# foe-scale2.net
KiCad netlist of a schematic drawn in EAGLE
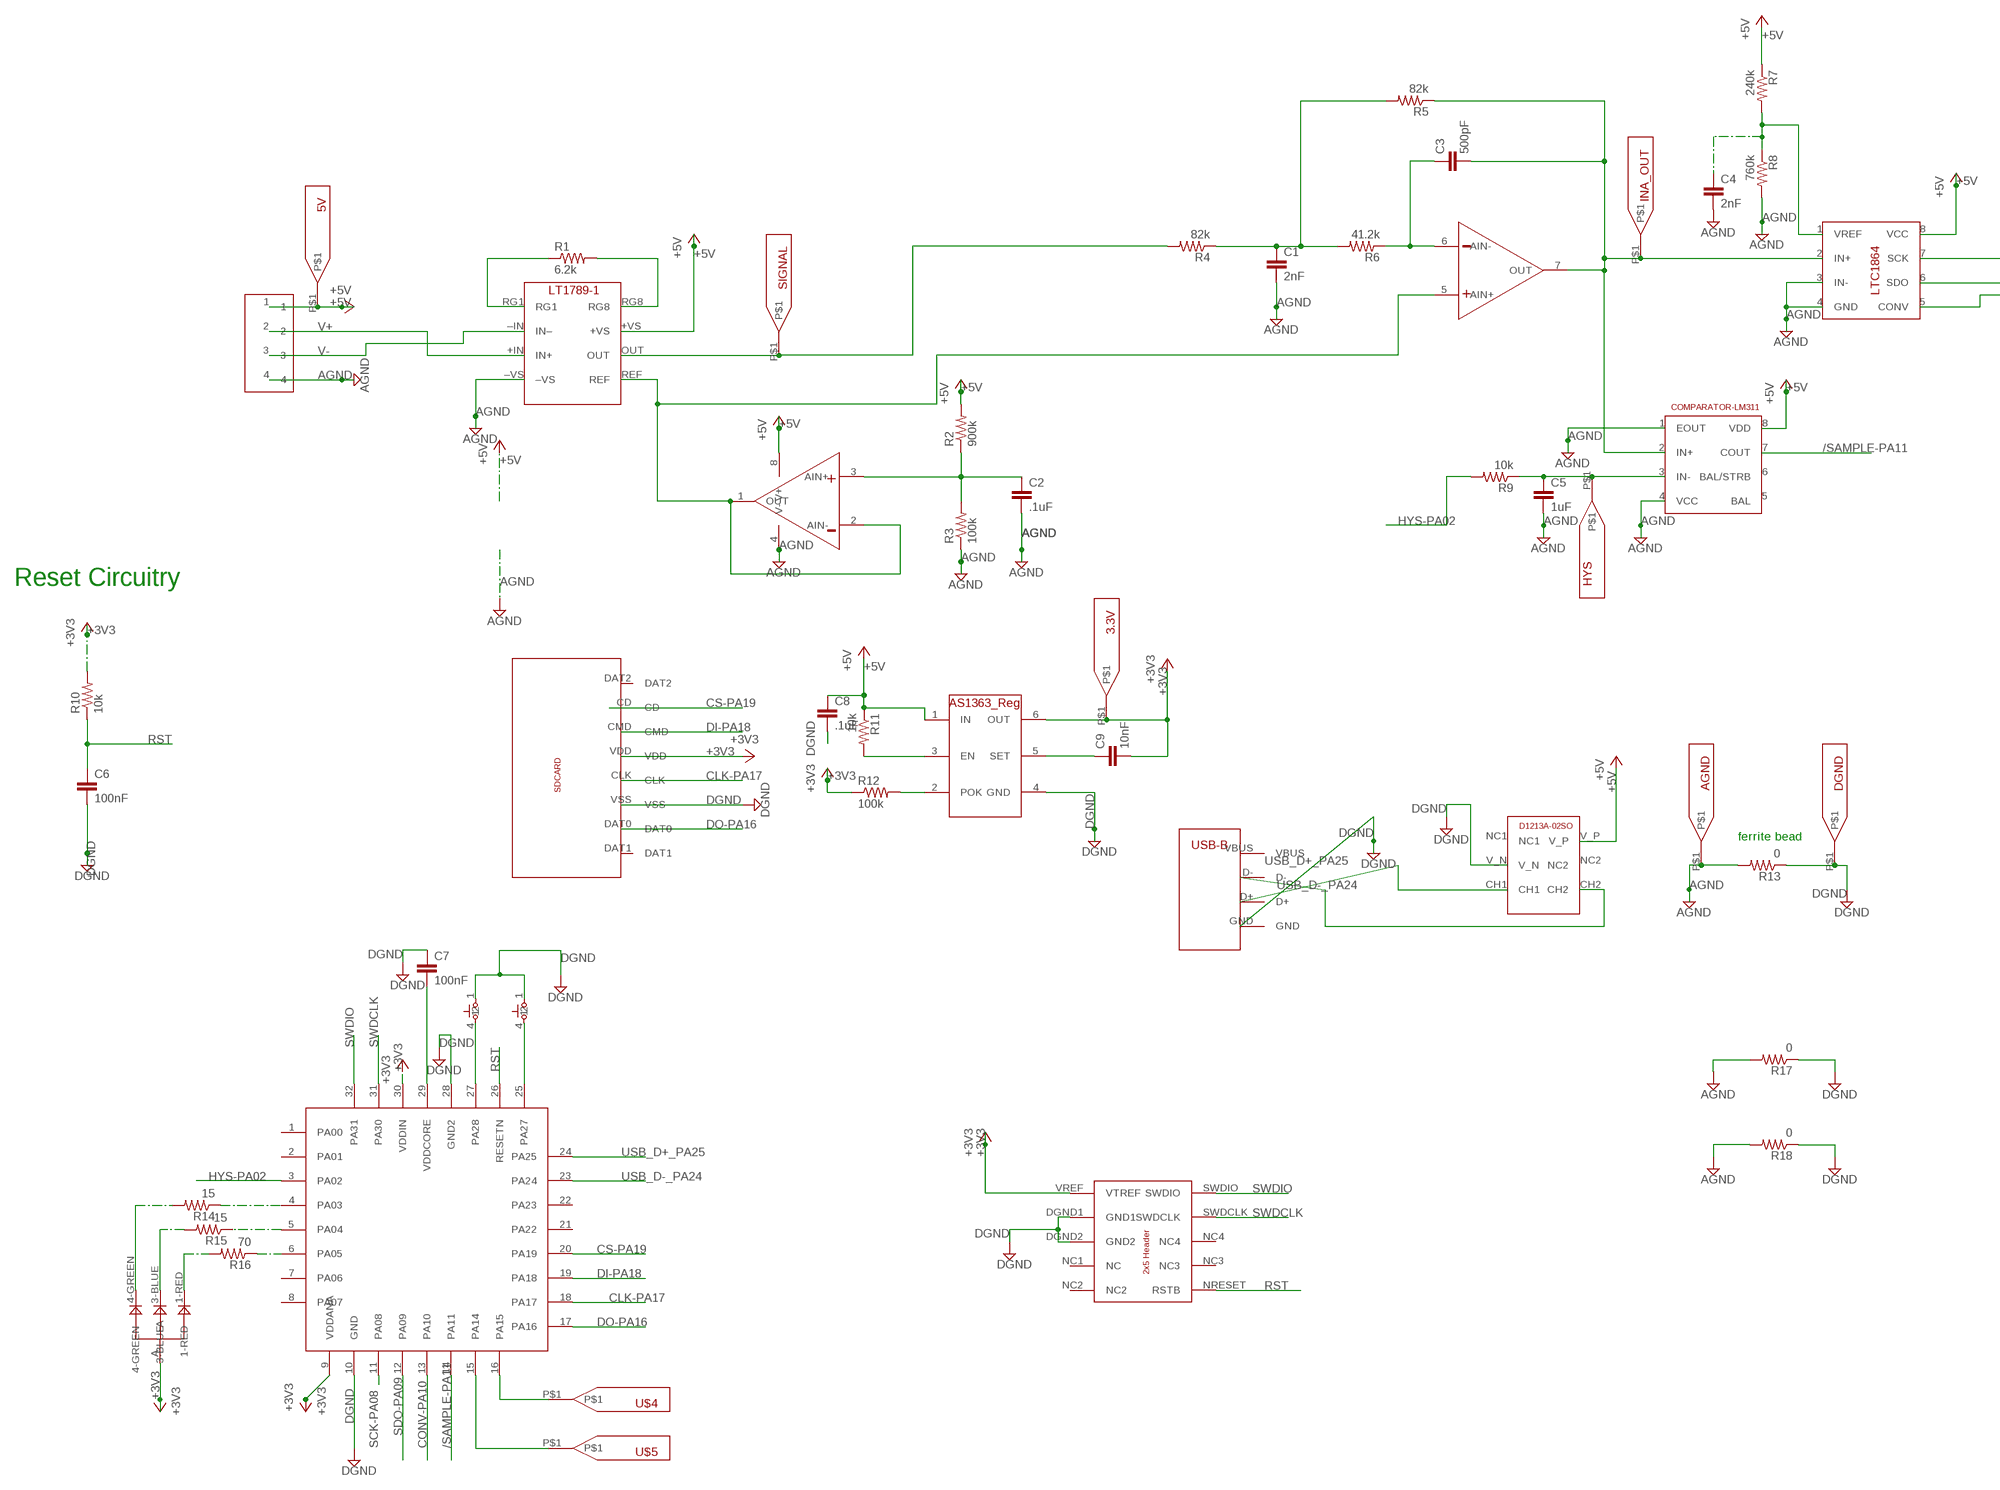
[diagram p0: schematic, sheet 1, part 1 of 2]
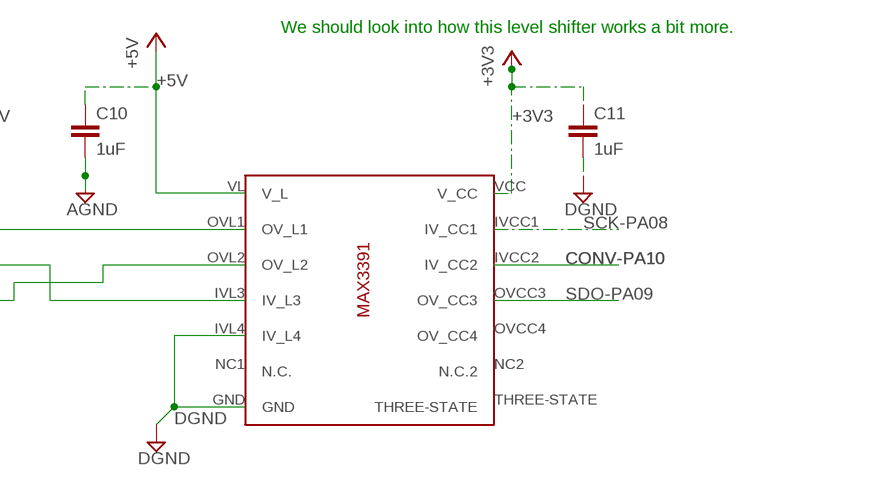
[diagram p1: schematic, sheet 1, part 2 of 2]

(export (version "E")
  (design (tool "Eeschema 10.0.6"))
  (components
    (comp (ref "3.3V")
      (value "TEST_POINT")
      (footprint "eagle-import:TEST_POINT")
      (libsource (lib "eagle-import") (part "TEST_POINT"))
    )
    (comp (ref "5V")
      (value "TEST_POINT")
      (footprint "eagle-import:TEST_POINT")
      (libsource (lib "eagle-import") (part "TEST_POINT"))
    )
    (comp (ref "AGND")
      (value "TEST_POINT")
      (footprint "eagle-import:TEST_POINT")
      (libsource (lib "eagle-import") (part "TEST_POINT"))
    )
    (comp (ref "AS1363")
      (value "3.3V_AS1363")
      (footprint "eagle-import:SOT23-6")
      (libsource (lib "eagle-import") (part "3.3V_AS1363"))
    )
    (comp (ref "C1")
      (value "2nF")
      (footprint "eagle-import:C0805K")
      (libsource (lib "eagle-import") (part "C-EUC0805K"))
    )
    (comp (ref "C2")
      (value ".1uF")
      (footprint "eagle-import:C0805K")
      (libsource (lib "eagle-import") (part "C-EUC0805K"))
    )
    (comp (ref "C3")
      (value "500pF")
      (footprint "eagle-import:C0805K")
      (libsource (lib "eagle-import") (part "C-EUC0805K"))
    )
    (comp (ref "C4")
      (value "2nF")
      (footprint "eagle-import:C0805K")
      (libsource (lib "eagle-import") (part "C-EUC0805K"))
    )
    (comp (ref "C5")
      (value "1uF")
      (footprint "eagle-import:C0805K")
      (libsource (lib "eagle-import") (part "C-EUC0805K"))
    )
    (comp (ref "C6")
      (value "100nF")
      (footprint "eagle-import:C0805K")
      (libsource (lib "eagle-import") (part "C-EUC0805K"))
    )
    (comp (ref "C7")
      (value "100nF")
      (footprint "eagle-import:C0805K")
      (libsource (lib "eagle-import") (part "C-EUC0805K"))
    )
    (comp (ref "C8")
      (value ".1uF")
      (footprint "eagle-import:C0805K")
      (libsource (lib "eagle-import") (part "C-EUC0805K"))
    )
    (comp (ref "C9")
      (value "10nF")
      (footprint "eagle-import:C0805K")
      (libsource (lib "eagle-import") (part "C-EUC0805K"))
    )
    (comp (ref "C10")
      (value "1uF")
      (footprint "eagle-import:C0805K")
      (libsource (lib "eagle-import") (part "C-EUC0805K"))
    )
    (comp (ref "C11")
      (value "1uF")
      (footprint "eagle-import:C0805K")
      (libsource (lib "eagle-import") (part "C-EUC0805K"))
    )
    (comp (ref "D1")
      (value "D1213A-DIODE-ARRAY")
      (footprint "eagle-import:SOT26-DIODE-ARRAY")
      (libsource (lib "eagle-import") (part "D1213A-DIODE-ARRAY"))
    )
    (comp (ref "DBG1")
      (value "DEBUGHEAD")
      (footprint "eagle-import:DEBUGHEAD")
      (libsource (lib "eagle-import") (part "DEBUGHEAD"))
    )
    (comp (ref "DGND")
      (value "TEST_POINT")
      (footprint "eagle-import:TEST_POINT")
      (libsource (lib "eagle-import") (part "TEST_POINT"))
    )
    (comp (ref "HYS")
      (value "TEST_POINT")
      (footprint "eagle-import:TEST_POINT")
      (libsource (lib "eagle-import") (part "TEST_POINT"))
    )
    (comp (ref "INA_OUT")
      (value "TEST_POINT")
      (footprint "eagle-import:TEST_POINT")
      (libsource (lib "eagle-import") (part "TEST_POINT"))
    )
    (comp (ref "R1")
      (value "6.2k")
      (footprint "eagle-import:R0805")
      (libsource (lib "eagle-import") (part "R-US_R0805"))
    )
    (comp (ref "R2")
      (value "900k")
      (footprint "eagle-import:R0805")
      (libsource (lib "eagle-import") (part "R-US_R0805"))
    )
    (comp (ref "R3")
      (value "100k")
      (footprint "eagle-import:R0805")
      (libsource (lib "eagle-import") (part "R-US_R0805"))
    )
    (comp (ref "R4")
      (value "82k")
      (footprint "eagle-import:R0805")
      (libsource (lib "eagle-import") (part "R-US_R0805"))
    )
    (comp (ref "R5")
      (value "82k")
      (footprint "eagle-import:R0805")
      (libsource (lib "eagle-import") (part "R-US_R0805"))
    )
    (comp (ref "R6")
      (value "41.2k")
      (footprint "eagle-import:R0805")
      (libsource (lib "eagle-import") (part "R-US_R0805"))
    )
    (comp (ref "R7")
      (value "240k")
      (footprint "eagle-import:R0805")
      (libsource (lib "eagle-import") (part "R-US_R0805"))
    )
    (comp (ref "R8")
      (value "760k")
      (footprint "eagle-import:R0805")
      (libsource (lib "eagle-import") (part "R-US_R0805"))
    )
    (comp (ref "R9")
      (value "10k")
      (footprint "eagle-import:R0805")
      (libsource (lib "eagle-import") (part "R-US_R0805"))
    )
    (comp (ref "R10")
      (value "10k")
      (footprint "eagle-import:R0805")
      (libsource (lib "eagle-import") (part "R-US_R0805"))
    )
    (comp (ref "R11")
      (value "10k")
      (footprint "eagle-import:R0805")
      (libsource (lib "eagle-import") (part "R-US_R0805"))
    )
    (comp (ref "R12")
      (value "100k")
      (footprint "eagle-import:R0805")
      (libsource (lib "eagle-import") (part "R-US_R0805"))
    )
    (comp (ref "R13")
      (value "0")
      (footprint "eagle-import:R0805")
      (libsource (lib "eagle-import") (part "R-US_R0805"))
    )
    (comp (ref "R14")
      (value "15")
      (footprint "eagle-import:R0805")
      (libsource (lib "eagle-import") (part "R-US_R0805"))
    )
    (comp (ref "R15")
      (value "15")
      (footprint "eagle-import:R0805")
      (libsource (lib "eagle-import") (part "R-US_R0805"))
    )
    (comp (ref "R16")
      (value "70")
      (footprint "eagle-import:R0805")
      (libsource (lib "eagle-import") (part "R-US_R0805"))
    )
    (comp (ref "R17")
      (value "0")
      (footprint "eagle-import:R0805")
      (libsource (lib "eagle-import") (part "R-US_R0805"))
    )
    (comp (ref "R18")
      (value "0")
      (footprint "eagle-import:R0805")
      (libsource (lib "eagle-import") (part "R-US_R0805"))
    )
    (comp (ref "SIGNAL")
      (value "TEST_POINT")
      (footprint "eagle-import:TEST_POINT")
      (libsource (lib "eagle-import") (part "TEST_POINT"))
    )
    (comp (ref "U$1")
      (value "1X04")
      (footprint "eagle-import:1X04")
      (libsource (lib "eagle-import") (part "1X04"))
    )
    (comp (ref "U$2")
      (value "LT1789-1-INSTR-AMP")
      (footprint "eagle-import:S8-LT1789-1")
      (libsource (lib "eagle-import") (part "LT1789-1-INSTR-AMP"))
    )
    (comp (ref "U$3")
      (value "LMC6482")
      (footprint "eagle-import:SOIC8")
      (libsource (lib "eagle-import") (part "LMC6482"))
    )
    (comp (ref "U$4")
      (value "TEST_POINT")
      (footprint "eagle-import:TEST_POINT")
      (libsource (lib "eagle-import") (part "TEST_POINT"))
    )
    (comp (ref "U$5")
      (value "TEST_POINT")
      (footprint "eagle-import:TEST_POINT")
      (libsource (lib "eagle-import") (part "TEST_POINT"))
    )
    (comp (ref "U$6")
      (value "ADC-LTC1864")
      (footprint "eagle-import:SOIC8")
      (libsource (lib "eagle-import") (part "ADC-LTC1864"))
    )
    (comp (ref "U$7")
      (value "LEVEL-SHIFTER")
      (footprint "eagle-import:TSSOP-14")
      (libsource (lib "eagle-import") (part "LEVEL-SHIFTER"))
    )
    (comp (ref "U$8")
      (value "SDCARD_JACK")
      (footprint "eagle-import:MICRO_SDCARD")
      (libsource (lib "eagle-import") (part "SDCARD_JACK"))
    )
    (comp (ref "U$10")
      (value "RGBLED")
      (footprint "eagle-import:RGBLED")
      (libsource (lib "eagle-import") (part "RGBLED"))
    )
    (comp (ref "U$11")
      (value "BUTTON_THRU")
      (footprint "eagle-import:PUSHBTN")
      (libsource (lib "eagle-import") (part "BUTTON_THRU"))
    )
    (comp (ref "U$12")
      (value "BUTTON_THRU")
      (footprint "eagle-import:PUSHBTN")
      (libsource (lib "eagle-import") (part "BUTTON_THRU"))
    )
    (comp (ref "U$13")
      (value "USB-B")
      (footprint "eagle-import:USB-B")
      (libsource (lib "eagle-import") (part "USB-B"))
    )
    (comp (ref "U1")
      (value "LM311")
      (footprint "eagle-import:SOIC8")
      (libsource (lib "eagle-import") (part "LM311"))
    )
    (comp (ref "U2")
      (value "SAMD21E")
      (footprint "eagle-import:TQFP32-08")
      (libsource (lib "eagle-import") (part "SAMD21E"))
    )
  )
  (nets
    (net (code "1") (name "+3V3") (class "Default")
      (node (ref "3.3V") (pin "P$1") (pinfunction "P$1_P$1") (pintype "bidirectional"))
      (node (ref "AS1363") (pin "6") (pinfunction "OUT_6") (pintype "bidirectional"))
      (node (ref "C11") (pin "1") (pinfunction "1_1") (pintype "passive"))
      (node (ref "C9") (pin "2") (pinfunction "2_2") (pintype "passive"))
      (node (ref "DBG1") (pin "VREF") (pinfunction "VTREF_VREF") (pintype "bidirectional"))
      (node (ref "R10") (pin "2") (pinfunction "2_2") (pintype "passive"))
      (node (ref "R12") (pin "1") (pinfunction "1_1") (pintype "passive"))
      (node (ref "U$10") (pin "A") (pinfunction "A_A") (pintype "bidirectional"))
      (node (ref "U$7") (pin "VCC") (pinfunction "V_CC_VCC") (pintype "bidirectional"))
      (node (ref "U$8") (pin "VDD") (pinfunction "VDD_VDD") (pintype "bidirectional"))
      (node (ref "U2") (pin "30") (pinfunction "VDDIN_30") (pintype "bidirectional"))
      (node (ref "U2") (pin "9") (pinfunction "VDDANA_9") (pintype "bidirectional"))
    )
    (net (code "2") (name "+5V") (class "Default")
      (node (ref "5V") (pin "P$1") (pinfunction "P$1_P$1") (pintype "bidirectional"))
      (node (ref "AS1363") (pin "1") (pinfunction "IN_1") (pintype "bidirectional"))
      (node (ref "C10") (pin "1") (pinfunction "1_1") (pintype "passive"))
      (node (ref "C8") (pin "1") (pinfunction "1_1") (pintype "passive"))
      (node (ref "D1") (pin "V_P") (pinfunction "V_P_V_P") (pintype "bidirectional"))
      (node (ref "R11") (pin "1") (pinfunction "1_1") (pintype "passive"))
      (node (ref "R2") (pin "2") (pinfunction "2_2") (pintype "passive"))
      (node (ref "R7") (pin "1") (pinfunction "1_1") (pintype "passive"))
      (node (ref "U$1") (pin "1") (pinfunction "1_1") (pintype "bidirectional"))
      (node (ref "U$2") (pin "+VS") (pinfunction "+VS_+VS") (pintype "bidirectional"))
      (node (ref "U$3") (pin "8") (pinfunction "V+_8") (pintype "bidirectional"))
      (node (ref "U$6") (pin "8") (pinfunction "VCC_8") (pintype "bidirectional"))
      (node (ref "U$7") (pin "VL") (pinfunction "V_L_VL") (pintype "bidirectional"))
      (node (ref "U1") (pin "8") (pinfunction "VDD_8") (pintype "bidirectional"))
    )
    (net (code "3") (name "/CLK-PA17") (class "Default")
      (node (ref "U$8") (pin "CLK") (pinfunction "CLK_CLK") (pintype "bidirectional"))
      (node (ref "U2") (pin "18") (pinfunction "PA17_18") (pintype "bidirectional"))
    )
    (net (code "4") (name "/CONV-PA10") (class "Default")
      (node (ref "U$7") (pin "IVCC2") (pinfunction "IV_CC2_IVCC2") (pintype "bidirectional"))
      (node (ref "U2") (pin "13") (pinfunction "PA10_13") (pintype "bidirectional"))
    )
    (net (code "5") (name "/CS-PA19") (class "Default")
      (node (ref "U$8") (pin "CD") (pinfunction "CD_CD") (pintype "bidirectional"))
      (node (ref "U2") (pin "20") (pinfunction "PA19_20") (pintype "bidirectional"))
    )
    (net (code "6") (name "/DI-PA18") (class "Default")
      (node (ref "U$8") (pin "CMD") (pinfunction "CMD_CMD") (pintype "bidirectional"))
      (node (ref "U2") (pin "19") (pinfunction "PA18_19") (pintype "bidirectional"))
    )
    (net (code "7") (name "/DO-PA16") (class "Default")
      (node (ref "U$8") (pin "DAT0") (pinfunction "DAT0_DAT0") (pintype "bidirectional"))
      (node (ref "U2") (pin "17") (pinfunction "PA16_17") (pintype "bidirectional"))
    )
    (net (code "8") (name "/HYS-PA02") (class "Default")
      (node (ref "R9") (pin "2") (pinfunction "2_2") (pintype "passive"))
      (node (ref "U2") (pin "3") (pinfunction "PA02_3") (pintype "bidirectional"))
    )
    (net (code "9") (name "/RST") (class "Default")
      (node (ref "C6") (pin "1") (pinfunction "1_1") (pintype "passive"))
      (node (ref "DBG1") (pin "NRESET") (pinfunction "RSTB_NRESET") (pintype "bidirectional"))
      (node (ref "R10") (pin "1") (pinfunction "1_1") (pintype "passive"))
      (node (ref "U2") (pin "26") (pinfunction "RESETN_26") (pintype "bidirectional"))
    )
    (net (code "10") (name "/SCK-PA08") (class "Default")
      (node (ref "U$7") (pin "IVCC1") (pinfunction "IV_CC1_IVCC1") (pintype "bidirectional"))
      (node (ref "U2") (pin "11") (pinfunction "PA08_11") (pintype "bidirectional"))
    )
    (net (code "11") (name "/SDO-PA09") (class "Default")
      (node (ref "U$7") (pin "OVCC3") (pinfunction "OV_CC3_OVCC3") (pintype "bidirectional"))
      (node (ref "U2") (pin "12") (pinfunction "PA09_12") (pintype "bidirectional"))
    )
    (net (code "12") (name "/SWDCLK") (class "Default")
      (node (ref "DBG1") (pin "SWDCLK") (pinfunction "SWDCLK_SWDCLK") (pintype "bidirectional"))
      (node (ref "U2") (pin "31") (pinfunction "PA30_31") (pintype "bidirectional"))
    )
    (net (code "13") (name "/SWDIO") (class "Default")
      (node (ref "DBG1") (pin "SWDIO") (pinfunction "SWDIO_SWDIO") (pintype "bidirectional"))
      (node (ref "U2") (pin "32") (pinfunction "PA31_32") (pintype "bidirectional"))
    )
    (net (code "14") (name "/USB_D+_PA25") (class "Default")
      (node (ref "D1") (pin "CH1") (pinfunction "CH1_CH1") (pintype "bidirectional"))
      (node (ref "U$13") (pin "D+") (pinfunction "D+_D+") (pintype "bidirectional"))
      (node (ref "U2") (pin "24") (pinfunction "PA25_24") (pintype "bidirectional"))
    )
    (net (code "15") (name "/USB_D-_PA24") (class "Default")
      (node (ref "D1") (pin "CH2") (pinfunction "CH2_CH2") (pintype "bidirectional"))
      (node (ref "U$13") (pin "D-") (pinfunction "D-_D-") (pintype "bidirectional"))
      (node (ref "U2") (pin "23") (pinfunction "PA24_23") (pintype "bidirectional"))
    )
    (net (code "16") (name "/V+") (class "Default")
      (node (ref "U$1") (pin "2") (pinfunction "2_2") (pintype "bidirectional"))
      (node (ref "U$2") (pin "+IN") (pinfunction "IN+_+IN") (pintype "bidirectional"))
    )
    (net (code "17") (name "/V-") (class "Default")
      (node (ref "U$1") (pin "3") (pinfunction "3_3") (pintype "bidirectional"))
      (node (ref "U$2") (pin "–IN") (pinfunction "IN–_–IN") (pintype "bidirectional"))
    )
    (net (code "18") (name "/{slash}SAMPLE-PA11") (class "Default")
      (node (ref "U1") (pin "7") (pinfunction "COUT_7") (pintype "bidirectional"))
      (node (ref "U2") (pin "14") (pinfunction "PA11_14") (pintype "bidirectional"))
    )
    (net (code "19") (name "AGND") (class "Default")
      (node (ref "AGND") (pin "P$1") (pinfunction "P$1_P$1") (pintype "bidirectional"))
      (node (ref "C1") (pin "2") (pinfunction "2_2") (pintype "passive"))
      (node (ref "C10") (pin "2") (pinfunction "2_2") (pintype "passive"))
      (node (ref "C2") (pin "2") (pinfunction "2_2") (pintype "passive"))
      (node (ref "C4") (pin "2") (pinfunction "2_2") (pintype "passive"))
      (node (ref "C5") (pin "2") (pinfunction "2_2") (pintype "passive"))
      (node (ref "R13") (pin "2") (pinfunction "2_2") (pintype "passive"))
      (node (ref "R17") (pin "2") (pinfunction "2_2") (pintype "passive"))
      (node (ref "R18") (pin "2") (pinfunction "2_2") (pintype "passive"))
      (node (ref "R3") (pin "1") (pinfunction "1_1") (pintype "passive"))
      (node (ref "R8") (pin "2") (pinfunction "2_2") (pintype "passive"))
      (node (ref "U$1") (pin "4") (pinfunction "4_4") (pintype "bidirectional"))
      (node (ref "U$2") (pin "–VS") (pinfunction "–VS_–VS") (pintype "bidirectional"))
      (node (ref "U$3") (pin "4") (pinfunction "V-_4") (pintype "bidirectional"))
      (node (ref "U$6") (pin "3") (pinfunction "IN-_3") (pintype "bidirectional"))
      (node (ref "U$6") (pin "4") (pinfunction "GND_4") (pintype "bidirectional"))
      (node (ref "U1") (pin "1") (pinfunction "EOUT_1") (pintype "bidirectional"))
      (node (ref "U1") (pin "4") (pinfunction "VCC_4") (pintype "bidirectional"))
    )
    (net (code "20") (name "DGND") (class "Default")
      (node (ref "AS1363") (pin "4") (pinfunction "GND_4") (pintype "bidirectional"))
      (node (ref "C11") (pin "2") (pinfunction "2_2") (pintype "passive"))
      (node (ref "C6") (pin "2") (pinfunction "2_2") (pintype "passive"))
      (node (ref "C7") (pin "1") (pinfunction "1_1") (pintype "passive"))
      (node (ref "C8") (pin "2") (pinfunction "2_2") (pintype "passive"))
      (node (ref "D1") (pin "V_N") (pinfunction "V_N_V_N") (pintype "bidirectional"))
      (node (ref "DBG1") (pin "DGND1") (pinfunction "GND1_DGND1") (pintype "bidirectional"))
      (node (ref "DBG1") (pin "DGND2") (pinfunction "GND2_DGND2") (pintype "bidirectional"))
      (node (ref "DGND") (pin "P$1") (pinfunction "P$1_P$1") (pintype "bidirectional"))
      (node (ref "R13") (pin "1") (pinfunction "1_1") (pintype "passive"))
      (node (ref "R17") (pin "1") (pinfunction "1_1") (pintype "passive"))
      (node (ref "R18") (pin "1") (pinfunction "1_1") (pintype "passive"))
      (node (ref "U$11") (pin "1") (pinfunction "1_1") (pintype "bidirectional"))
      (node (ref "U$12") (pin "1") (pinfunction "1_1") (pintype "bidirectional"))
      (node (ref "U$13") (pin "GND") (pinfunction "GND_GND") (pintype "bidirectional"))
      (node (ref "U$7") (pin "GND") (pinfunction "GND_GND") (pintype "bidirectional"))
      (node (ref "U$7") (pin "IVL4") (pinfunction "IV_L4_IVL4") (pintype "bidirectional"))
      (node (ref "U$8") (pin "VSS") (pinfunction "VSS_VSS") (pintype "bidirectional"))
      (node (ref "U2") (pin "10") (pinfunction "GND_10") (pintype "bidirectional"))
      (node (ref "U2") (pin "28") (pinfunction "GND2_28") (pintype "bidirectional"))
    )
    (net (code "21") (name "Net-(AS1363-EN)") (class "Default")
      (node (ref "AS1363") (pin "3") (pinfunction "EN_3") (pintype "bidirectional"))
      (node (ref "R11") (pin "2") (pinfunction "2_2") (pintype "passive"))
    )
    (net (code "22") (name "Net-(AS1363-POK)") (class "Default")
      (node (ref "AS1363") (pin "2") (pinfunction "POK_2") (pintype "bidirectional"))
      (node (ref "R12") (pin "2") (pinfunction "2_2") (pintype "passive"))
    )
    (net (code "23") (name "Net-(AS1363-SET)") (class "Default")
      (node (ref "AS1363") (pin "5") (pinfunction "SET_5") (pintype "bidirectional"))
      (node (ref "C9") (pin "1") (pinfunction "1_1") (pintype "passive"))
    )
    (net (code "24") (name "Net-(C1-Pad1)") (class "Default")
      (node (ref "C1") (pin "1") (pinfunction "1_1") (pintype "passive"))
      (node (ref "R4") (pin "1") (pinfunction "1_1") (pintype "passive"))
      (node (ref "R5") (pin "2") (pinfunction "2_2") (pintype "passive"))
      (node (ref "R6") (pin "2") (pinfunction "2_2") (pintype "passive"))
    )
    (net (code "25") (name "Net-(R1-Pad1)") (class "Default")
      (node (ref "R1") (pin "1") (pinfunction "1_1") (pintype "passive"))
      (node (ref "U$2") (pin "RG1") (pinfunction "RG1_RG1") (pintype "bidirectional"))
    )
    (net (code "26") (name "Net-(R1-Pad2)") (class "Default")
      (node (ref "R1") (pin "2") (pinfunction "2_2") (pintype "passive"))
      (node (ref "U$2") (pin "RG8") (pinfunction "RG8_RG8") (pintype "bidirectional"))
    )
    (net (code "27") (name "Net-(R4-Pad2)") (class "Default")
      (node (ref "R4") (pin "2") (pinfunction "2_2") (pintype "passive"))
      (node (ref "SIGNAL") (pin "P$1") (pinfunction "P$1_P$1") (pintype "bidirectional"))
      (node (ref "U$2") (pin "OUT") (pinfunction "OUT_OUT") (pintype "bidirectional"))
    )
    (net (code "28") (name "Net-(R14-Pad2)") (class "Default")
      (node (ref "R14") (pin "2") (pinfunction "2_2") (pintype "passive"))
      (node (ref "U$10") (pin "4-GREEN") (pinfunction "4-GREEN_4-GREEN") (pintype "bidirectional"))
    )
    (net (code "29") (name "Net-(R15-Pad2)") (class "Default")
      (node (ref "R15") (pin "2") (pinfunction "2_2") (pintype "passive"))
      (node (ref "U$10") (pin "3-BLUE") (pinfunction "3-BLUE_3-BLUE") (pintype "bidirectional"))
    )
    (net (code "30") (name "Net-(R16-Pad2)") (class "Default")
      (node (ref "R16") (pin "2") (pinfunction "2_2") (pintype "passive"))
      (node (ref "U$10") (pin "1-RED") (pinfunction "1-RED_1-RED") (pintype "bidirectional"))
    )
    (net (code "31") (name "Net-(U$3A-AIN+)") (class "Default")
      (node (ref "C2") (pin "1") (pinfunction "1_1") (pintype "passive"))
      (node (ref "R2") (pin "1") (pinfunction "1_1") (pintype "passive"))
      (node (ref "R3") (pin "2") (pinfunction "2_2") (pintype "passive"))
      (node (ref "U$3") (pin "3") (pinfunction "AIN+_3") (pintype "bidirectional"))
    )
    (net (code "32") (name "Net-(U$3A-AIN-)") (class "Default")
      (node (ref "U$2") (pin "REF") (pinfunction "REF_REF") (pintype "bidirectional"))
      (node (ref "U$3") (pin "1") (pinfunction "OUT_1") (pintype "bidirectional"))
      (node (ref "U$3") (pin "2") (pinfunction "AIN-_2") (pintype "bidirectional"))
      (node (ref "U$3") (pin "5") (pinfunction "AIN+_5") (pintype "bidirectional"))
    )
    (net (code "33") (name "Net-(U$3B-AIN-)") (class "Default")
      (node (ref "C3") (pin "1") (pinfunction "1_1") (pintype "passive"))
      (node (ref "R6") (pin "1") (pinfunction "1_1") (pintype "passive"))
      (node (ref "U$3") (pin "6") (pinfunction "AIN-_6") (pintype "bidirectional"))
    )
    (net (code "34") (name "Net-(U$3B-OUT)") (class "Default")
      (node (ref "C3") (pin "2") (pinfunction "2_2") (pintype "passive"))
      (node (ref "INA_OUT") (pin "P$1") (pinfunction "P$1_P$1") (pintype "bidirectional"))
      (node (ref "R5") (pin "1") (pinfunction "1_1") (pintype "passive"))
      (node (ref "U$3") (pin "7") (pinfunction "OUT_7") (pintype "bidirectional"))
      (node (ref "U$6") (pin "2") (pinfunction "IN+_2") (pintype "bidirectional"))
      (node (ref "U1") (pin "2") (pinfunction "IN+_2") (pintype "bidirectional"))
    )
    (net (code "35") (name "Net-(U$6-CONV)") (class "Default")
      (node (ref "U$6") (pin "5") (pinfunction "CONV_5") (pintype "bidirectional"))
      (node (ref "U$7") (pin "OVL2") (pinfunction "OV_L2_OVL2") (pintype "bidirectional"))
    )
    (net (code "36") (name "Net-(U$6-SCK)") (class "Default")
      (node (ref "U$6") (pin "7") (pinfunction "SCK_7") (pintype "bidirectional"))
      (node (ref "U$7") (pin "OVL1") (pinfunction "OV_L1_OVL1") (pintype "bidirectional"))
    )
    (net (code "37") (name "Net-(U$6-SDO)") (class "Default")
      (node (ref "U$6") (pin "6") (pinfunction "SDO_6") (pintype "bidirectional"))
      (node (ref "U$7") (pin "IVL3") (pinfunction "IV_L3_IVL3") (pintype "bidirectional"))
    )
    (net (code "38") (name "Net-(U$6-VREF)") (class "Default")
      (node (ref "C4") (pin "1") (pinfunction "1_1") (pintype "passive"))
      (node (ref "R7") (pin "2") (pinfunction "2_2") (pintype "passive"))
      (node (ref "R8") (pin "1") (pinfunction "1_1") (pintype "passive"))
      (node (ref "U$6") (pin "1") (pinfunction "VREF_1") (pintype "bidirectional"))
    )
    (net (code "39") (name "Net-(U$11-2)") (class "Default")
      (node (ref "U$11") (pin "4") (pinfunction "2_4") (pintype "bidirectional"))
      (node (ref "U2") (pin "25") (pinfunction "PA27_25") (pintype "bidirectional"))
    )
    (net (code "40") (name "Net-(U$12-2)") (class "Default")
      (node (ref "U$12") (pin "4") (pinfunction "2_4") (pintype "bidirectional"))
      (node (ref "U2") (pin "27") (pinfunction "PA28_27") (pintype "bidirectional"))
    )
    (net (code "41") (name "Net-(U1-IN-)") (class "Default")
      (node (ref "C5") (pin "1") (pinfunction "1_1") (pintype "passive"))
      (node (ref "HYS") (pin "P$1") (pinfunction "P$1_P$1") (pintype "bidirectional"))
      (node (ref "R9") (pin "1") (pinfunction "1_1") (pintype "passive"))
      (node (ref "U1") (pin "3") (pinfunction "IN-_3") (pintype "bidirectional"))
    )
    (net (code "42") (name "Net-(U2-PA03)") (class "Default")
      (node (ref "R14") (pin "1") (pinfunction "1_1") (pintype "passive"))
      (node (ref "U2") (pin "4") (pinfunction "PA03_4") (pintype "bidirectional"))
    )
    (net (code "43") (name "Net-(U2-PA04)") (class "Default")
      (node (ref "R15") (pin "1") (pinfunction "1_1") (pintype "passive"))
      (node (ref "U2") (pin "5") (pinfunction "PA04_5") (pintype "bidirectional"))
    )
    (net (code "44") (name "Net-(U2-PA05)") (class "Default")
      (node (ref "R16") (pin "1") (pinfunction "1_1") (pintype "passive"))
      (node (ref "U2") (pin "6") (pinfunction "PA05_6") (pintype "bidirectional"))
    )
    (net (code "45") (name "Net-(U2-PA14)") (class "Default")
      (node (ref "U$5") (pin "P$1") (pinfunction "P$1_P$1") (pintype "bidirectional"))
      (node (ref "U2") (pin "15") (pinfunction "PA14_15") (pintype "bidirectional"))
    )
    (net (code "46") (name "Net-(U2-PA15)") (class "Default")
      (node (ref "U$4") (pin "P$1") (pinfunction "P$1_P$1") (pintype "bidirectional"))
      (node (ref "U2") (pin "16") (pinfunction "PA15_16") (pintype "bidirectional"))
    )
    (net (code "47") (name "Net-(U2-VDDCORE)") (class "Default")
      (node (ref "C7") (pin "2") (pinfunction "2_2") (pintype "passive"))
      (node (ref "U2") (pin "29") (pinfunction "VDDCORE_29") (pintype "bidirectional"))
    )
    (net (code "48") (name "unconnected-(D1-PadNC1)") (class "Default")
      (node (ref "D1") (pin "NC1") (pinfunction "NC1_NC1") (pintype "bidirectional"))
    )
    (net (code "49") (name "unconnected-(D1-PadNC2)") (class "Default")
      (node (ref "D1") (pin "NC2") (pinfunction "NC2_NC2") (pintype "bidirectional"))
    )
    (net (code "50") (name "unconnected-(DBG1-NC-PadNC1)") (class "Default")
      (node (ref "DBG1") (pin "NC1") (pinfunction "NC_NC1") (pintype "bidirectional"))
    )
    (net (code "51") (name "unconnected-(DBG1-PadNC2)") (class "Default")
      (node (ref "DBG1") (pin "NC2") (pinfunction "NC2_NC2") (pintype "bidirectional"))
    )
    (net (code "52") (name "unconnected-(DBG1-PadNC3)") (class "Default")
      (node (ref "DBG1") (pin "NC3") (pinfunction "NC3_NC3") (pintype "bidirectional"))
    )
    (net (code "53") (name "unconnected-(DBG1-PadNC4)") (class "Default")
      (node (ref "DBG1") (pin "NC4") (pinfunction "NC4_NC4") (pintype "bidirectional"))
    )
    (net (code "54") (name "unconnected-(U$7-N.C.-PadNC1)") (class "Default")
      (node (ref "U$7") (pin "NC1") (pinfunction "N.C._NC1") (pintype "bidirectional"))
    )
    (net (code "55") (name "unconnected-(U$7-N.C.2-PadNC2)") (class "Default")
      (node (ref "U$7") (pin "NC2") (pinfunction "N.C.2_NC2") (pintype "bidirectional"))
    )
    (net (code "56") (name "unconnected-(U$7-OV_CC4-PadOVCC4)") (class "Default")
      (node (ref "U$7") (pin "OVCC4") (pinfunction "OV_CC4_OVCC4") (pintype "bidirectional"))
    )
    (net (code "57") (name "unconnected-(U$7-PadTHREE-STATE)") (class "Default")
      (node (ref "U$7") (pin "THREE-STATE") (pinfunction "THREE-STATE_THREE-STATE") (pintype "bidirectional"))
    )
    (net (code "58") (name "unconnected-(U$8-PadDAT1)") (class "Default")
      (node (ref "U$8") (pin "DAT1") (pinfunction "DAT1_DAT1") (pintype "bidirectional"))
    )
    (net (code "59") (name "unconnected-(U$8-PadDAT2)") (class "Default")
      (node (ref "U$8") (pin "DAT2") (pinfunction "DAT2_DAT2") (pintype "bidirectional"))
    )
    (net (code "60") (name "unconnected-(U$13-PadVBUS)") (class "Default")
      (node (ref "U$13") (pin "VBUS") (pinfunction "VBUS_VBUS") (pintype "bidirectional"))
    )
    (net (code "61") (name "unconnected-(U1-BAL-Pad5)") (class "Default")
      (node (ref "U1") (pin "5") (pinfunction "BAL_5") (pintype "bidirectional"))
    )
    (net (code "62") (name "unconnected-(U1-BAL{slash}STRB-Pad6)") (class "Default")
      (node (ref "U1") (pin "6") (pinfunction "BAL/STRB_6") (pintype "bidirectional"))
    )
    (net (code "63") (name "unconnected-(U2-PA00-Pad1)") (class "Default")
      (node (ref "U2") (pin "1") (pinfunction "PA00_1") (pintype "bidirectional"))
    )
    (net (code "64") (name "unconnected-(U2-PA01-Pad2)") (class "Default")
      (node (ref "U2") (pin "2") (pinfunction "PA01_2") (pintype "bidirectional"))
    )
    (net (code "65") (name "unconnected-(U2-PA06-Pad7)") (class "Default")
      (node (ref "U2") (pin "7") (pinfunction "PA06_7") (pintype "bidirectional"))
    )
    (net (code "66") (name "unconnected-(U2-PA07-Pad8)") (class "Default")
      (node (ref "U2") (pin "8") (pinfunction "PA07_8") (pintype "bidirectional"))
    )
    (net (code "67") (name "unconnected-(U2-PA22-Pad21)") (class "Default")
      (node (ref "U2") (pin "21") (pinfunction "PA22_21") (pintype "bidirectional"))
    )
    (net (code "68") (name "unconnected-(U2-PA23-Pad22)") (class "Default")
      (node (ref "U2") (pin "22") (pinfunction "PA23_22") (pintype "bidirectional"))
    )
  )
)
